# deadlocks.net
KiCad netlist of a schematic drawn in EAGLE
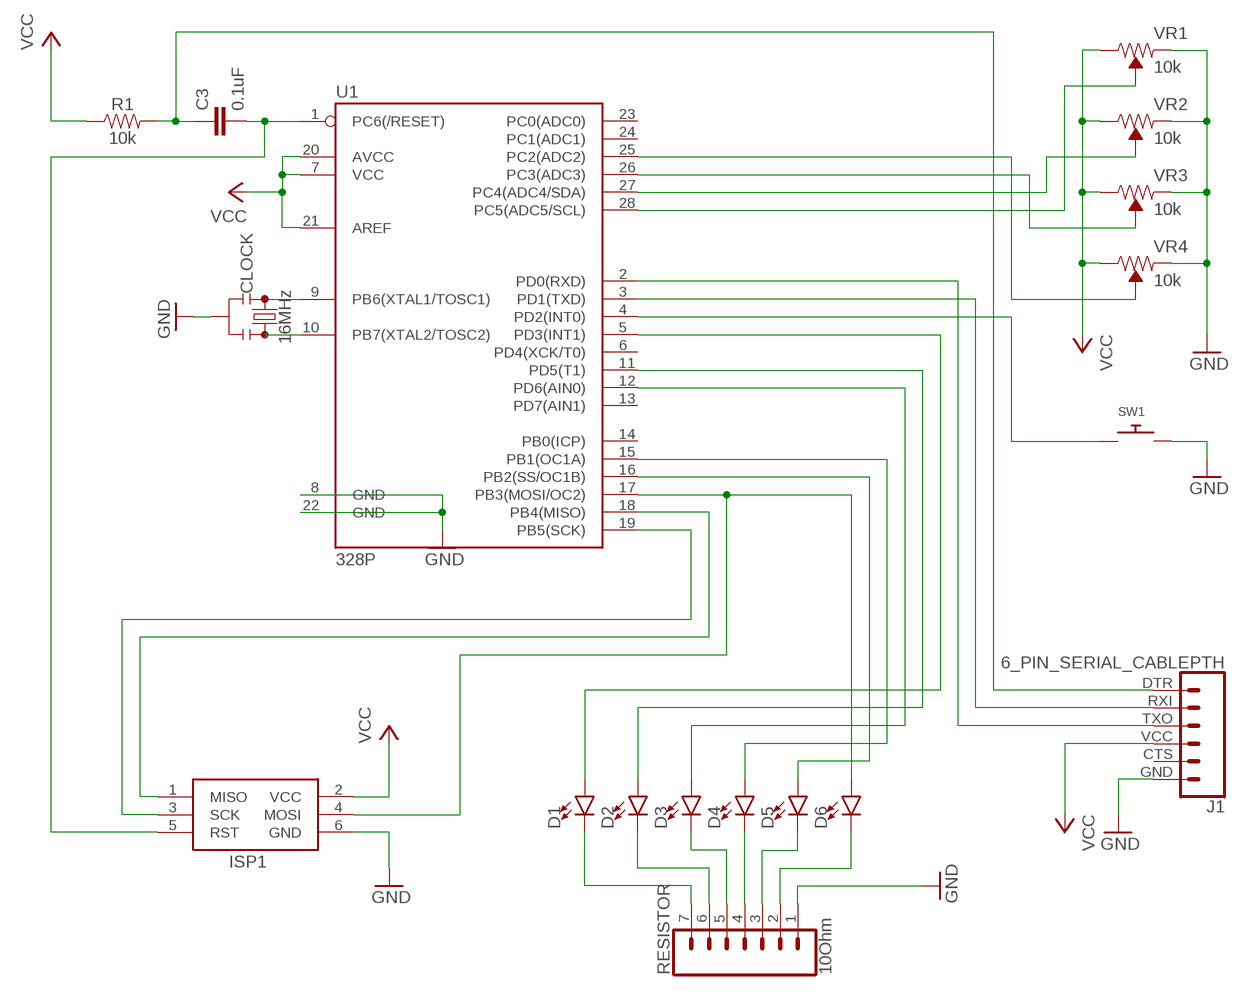
[diagram p0: schematic, sheet 1]

(export (version "E")
  (design (tool "Eeschema 10.0.6"))
  (components
    (comp (ref "C3")
      (value "0.1uF")
      (footprint "eagle-import:CAP-PTH-SMALL-KIT")
      (libsource (lib "eagle-import") (part "0.1UF-KIT-EZ-50V-20%"))
    )
    (comp (ref "CLOCK")
      (value "16MHz")
      (footprint "eagle-import:RESONATOR-PTH-7.6X3.8")
      (libsource (lib "eagle-import") (part "RESONATORPTH-7.6X3.8"))
    )
    (comp (ref "D1")
      (value "LED5MM")
      (footprint "eagle-import:LED_5MM")
      (libsource (lib "eagle-import") (part "LED5MM"))
    )
    (comp (ref "D2")
      (value "LED5MM")
      (footprint "eagle-import:LED_5MM")
      (libsource (lib "eagle-import") (part "LED5MM"))
    )
    (comp (ref "D3")
      (value "LED5MM")
      (footprint "eagle-import:LED_5MM")
      (libsource (lib "eagle-import") (part "LED5MM"))
    )
    (comp (ref "D4")
      (value "LED5MM")
      (footprint "eagle-import:LED_5MM")
      (libsource (lib "eagle-import") (part "LED5MM"))
    )
    (comp (ref "D5")
      (value "LED5MM")
      (footprint "eagle-import:LED_5MM")
      (libsource (lib "eagle-import") (part "LED5MM"))
    )
    (comp (ref "D6")
      (value "LED5MM")
      (footprint "eagle-import:LED_5MM")
      (libsource (lib "eagle-import") (part "LED5MM"))
    )
    (comp (ref "ISP1")
      (value "AVRISP-6")
      (footprint "eagle-import:AVRISP")
      (libsource (lib "eagle-import") (part "AVRISP-6"))
    )
    (comp (ref "J1")
      (value "6_PIN_SERIAL_CABLEPTH")
      (footprint "eagle-import:FTDI_BASIC")
      (libsource (lib "eagle-import") (part "6_PIN_SERIAL_CABLEPTH"))
    )
    (comp (ref "R1")
      (value "10k")
      (footprint "eagle-import:AXIAL-0.3")
      (libsource (lib "eagle-import") (part "10KOHM-HORIZ-1/4W-1%"))
    )
    (comp (ref "RESISTOR")
      (value "10Ohm")
      (footprint "eagle-import:1X07")
      (libsource (lib "eagle-import") (part "CONN_07"))
    )
    (comp (ref "SW1")
      (value "SWITCH_PUSHBUTTONEVQ-PE")
      (footprint "eagle-import:TACT_PANA-EVQ")
      (libsource (lib "eagle-import") (part "SWITCH_PUSHBUTTONEVQ-PE"))
    )
    (comp (ref "U1")
      (value "328P")
      (footprint "eagle-import:DIP28")
      (libsource (lib "eagle-import") (part "ATMEGA328P_PDIP"))
    )
    (comp (ref "VR1")
      (value "10k")
      (footprint "eagle-import:TRIMPOT-PTH-3386U")
      (libsource (lib "eagle-import") (part "TRIMPOT-PTH-10MM-KNOB-1/2W-10%"))
    )
    (comp (ref "VR2")
      (value "10k")
      (footprint "eagle-import:TRIMPOT-PTH-3386U")
      (libsource (lib "eagle-import") (part "TRIMPOT-PTH-10MM-KNOB-1/2W-10%"))
    )
    (comp (ref "VR3")
      (value "10k")
      (footprint "eagle-import:TRIMPOT-PTH-3386U")
      (libsource (lib "eagle-import") (part "TRIMPOT-PTH-10MM-KNOB-1/2W-10%"))
    )
    (comp (ref "VR4")
      (value "10k")
      (footprint "eagle-import:TRIMPOT-PTH-3386U")
      (libsource (lib "eagle-import") (part "TRIMPOT-PTH-10MM-KNOB-1/2W-10%"))
    )
  )
  (nets
    (net (code "1") (name "GND") (class "Default")
      (node (ref "CLOCK") (pin "2") (pinfunction "2_2") (pintype "passive"))
      (node (ref "ISP1") (pin "6") (pinfunction "GND_6") (pintype "power_in"))
      (node (ref "J1") (pin "GND") (pinfunction "6_GND") (pintype "passive"))
      (node (ref "RESISTOR") (pin "1") (pinfunction "1_1") (pintype "passive"))
      (node (ref "SW1") (pin "P$2") (pinfunction "P$2_P$2") (pintype "passive"))
      (node (ref "U1") (pin "22") (pinfunction "GND_22") (pintype "bidirectional"))
      (node (ref "U1") (pin "8") (pinfunction "GND_8") (pintype "bidirectional"))
      (node (ref "VR1") (pin "1") (pinfunction "CCW_1") (pintype "passive"))
      (node (ref "VR2") (pin "1") (pinfunction "CCW_1") (pintype "passive"))
      (node (ref "VR3") (pin "1") (pinfunction "CCW_1") (pintype "passive"))
      (node (ref "VR4") (pin "1") (pinfunction "CCW_1") (pintype "passive"))
    )
    (net (code "2") (name "Net-(D1-C)") (class "Default")
      (node (ref "D1") (pin "K") (pinfunction "C_K") (pintype "passive"))
      (node (ref "RESISTOR") (pin "7") (pinfunction "7_7") (pintype "passive"))
    )
    (net (code "3") (name "Net-(D2-C)") (class "Default")
      (node (ref "D2") (pin "K") (pinfunction "C_K") (pintype "passive"))
      (node (ref "RESISTOR") (pin "6") (pinfunction "6_6") (pintype "passive"))
    )
    (net (code "4") (name "Net-(D3-C)") (class "Default")
      (node (ref "D3") (pin "K") (pinfunction "C_K") (pintype "passive"))
      (node (ref "RESISTOR") (pin "5") (pinfunction "5_5") (pintype "passive"))
    )
    (net (code "5") (name "Net-(D4-C)") (class "Default")
      (node (ref "D4") (pin "K") (pinfunction "C_K") (pintype "passive"))
      (node (ref "RESISTOR") (pin "4") (pinfunction "4_4") (pintype "passive"))
    )
    (net (code "6") (name "Net-(D5-C)") (class "Default")
      (node (ref "D5") (pin "K") (pinfunction "C_K") (pintype "passive"))
      (node (ref "RESISTOR") (pin "3") (pinfunction "3_3") (pintype "passive"))
    )
    (net (code "7") (name "Net-(D6-C)") (class "Default")
      (node (ref "D6") (pin "K") (pinfunction "C_K") (pintype "passive"))
      (node (ref "RESISTOR") (pin "2") (pinfunction "2_2") (pintype "passive"))
    )
    (net (code "8") (name "Net-(ISP1-MISO)") (class "Default")
      (node (ref "ISP1") (pin "1") (pinfunction "MISO_1") (pintype "input"))
      (node (ref "U1") (pin "18") (pinfunction "PB4(MISO)_18") (pintype "bidirectional"))
    )
    (net (code "9") (name "Net-(ISP1-MOSI)") (class "Default")
      (node (ref "D6") (pin "A") (pinfunction "A_A") (pintype "passive"))
      (node (ref "ISP1") (pin "4") (pinfunction "MOSI_4") (pintype "output"))
      (node (ref "U1") (pin "17") (pinfunction "PB3(MOSI/OC2)_17") (pintype "bidirectional"))
    )
    (net (code "10") (name "Net-(ISP1-RST)") (class "Default")
      (node (ref "C3") (pin "2") (pinfunction "2_2") (pintype "passive"))
      (node (ref "ISP1") (pin "5") (pinfunction "RST_5") (pintype "output"))
      (node (ref "U1") (pin "1") (pinfunction "PC6(/RESET)_1") (pintype "bidirectional"))
    )
    (net (code "11") (name "Net-(ISP1-SCK)") (class "Default")
      (node (ref "ISP1") (pin "3") (pinfunction "SCK_3") (pintype "output"))
      (node (ref "U1") (pin "19") (pinfunction "PB5(SCK)_19") (pintype "bidirectional"))
    )
    (net (code "12") (name "Net-(J1-1)") (class "Default")
      (node (ref "C3") (pin "1") (pinfunction "1_1") (pintype "passive"))
      (node (ref "J1") (pin "DTR") (pinfunction "1_DTR") (pintype "passive"))
      (node (ref "R1") (pin "P$2") (pinfunction "2_P$2") (pintype "passive"))
    )
    (net (code "13") (name "Net-(J1-2)") (class "Default")
      (node (ref "J1") (pin "RXI") (pinfunction "2_RXI") (pintype "passive"))
      (node (ref "U1") (pin "3") (pinfunction "PD1(TXD)_3") (pintype "bidirectional"))
    )
    (net (code "14") (name "Net-(J1-3)") (class "Default")
      (node (ref "J1") (pin "TXO") (pinfunction "3_TXO") (pintype "passive"))
      (node (ref "U1") (pin "2") (pinfunction "PD0(RXD)_2") (pintype "bidirectional"))
    )
    (net (code "15") (name "Net-(U1-PB1(OC1A))") (class "Default")
      (node (ref "D4") (pin "A") (pinfunction "A_A") (pintype "passive"))
      (node (ref "U1") (pin "15") (pinfunction "PB1(OC1A)_15") (pintype "bidirectional"))
    )
    (net (code "16") (name "Net-(U1-PB2(SS{slash}OC1B))") (class "Default")
      (node (ref "D5") (pin "A") (pinfunction "A_A") (pintype "passive"))
      (node (ref "U1") (pin "16") (pinfunction "PB2(SS/OC1B)_16") (pintype "bidirectional"))
    )
    (net (code "17") (name "Net-(U1-PB6(XTAL1{slash}TOSC1))") (class "Default")
      (node (ref "CLOCK") (pin "1") (pinfunction "1_1") (pintype "passive"))
      (node (ref "U1") (pin "9") (pinfunction "PB6(XTAL1/TOSC1)_9") (pintype "bidirectional"))
    )
    (net (code "18") (name "Net-(U1-PB7(XTAL2{slash}TOSC2))") (class "Default")
      (node (ref "CLOCK") (pin "3") (pinfunction "3_3") (pintype "passive"))
      (node (ref "U1") (pin "10") (pinfunction "PB7(XTAL2/TOSC2)_10") (pintype "bidirectional"))
    )
    (net (code "19") (name "Net-(U1-PC2(ADC2))") (class "Default")
      (node (ref "U1") (pin "25") (pinfunction "PC2(ADC2)_25") (pintype "bidirectional"))
      (node (ref "VR4") (pin "2") (pinfunction "WIPER_2") (pintype "passive"))
    )
    (net (code "20") (name "Net-(U1-PC3(ADC3))") (class "Default")
      (node (ref "U1") (pin "26") (pinfunction "PC3(ADC3)_26") (pintype "bidirectional"))
      (node (ref "VR3") (pin "2") (pinfunction "WIPER_2") (pintype "passive"))
    )
    (net (code "21") (name "Net-(U1-PC4(ADC4{slash}SDA))") (class "Default")
      (node (ref "U1") (pin "27") (pinfunction "PC4(ADC4/SDA)_27") (pintype "bidirectional"))
      (node (ref "VR2") (pin "2") (pinfunction "WIPER_2") (pintype "passive"))
    )
    (net (code "22") (name "Net-(U1-PC5(ADC5{slash}SCL))") (class "Default")
      (node (ref "U1") (pin "28") (pinfunction "PC5(ADC5/SCL)_28") (pintype "bidirectional"))
      (node (ref "VR1") (pin "2") (pinfunction "WIPER_2") (pintype "passive"))
    )
    (net (code "23") (name "Net-(U1-PD2(INT0))") (class "Default")
      (node (ref "SW1") (pin "P$1") (pinfunction "P$1_P$1") (pintype "passive"))
      (node (ref "U1") (pin "4") (pinfunction "PD2(INT0)_4") (pintype "bidirectional"))
    )
    (net (code "24") (name "Net-(U1-PD3(INT1))") (class "Default")
      (node (ref "D1") (pin "A") (pinfunction "A_A") (pintype "passive"))
      (node (ref "U1") (pin "5") (pinfunction "PD3(INT1)_5") (pintype "bidirectional"))
    )
    (net (code "25") (name "Net-(U1-PD5(T1))") (class "Default")
      (node (ref "D2") (pin "A") (pinfunction "A_A") (pintype "passive"))
      (node (ref "U1") (pin "11") (pinfunction "PD5(T1)_11") (pintype "bidirectional"))
    )
    (net (code "26") (name "Net-(U1-PD6(AIN0))") (class "Default")
      (node (ref "D3") (pin "A") (pinfunction "A_A") (pintype "passive"))
      (node (ref "U1") (pin "12") (pinfunction "PD6(AIN0)_12") (pintype "bidirectional"))
    )
    (net (code "27") (name "VCC") (class "Default")
      (node (ref "ISP1") (pin "2") (pinfunction "VCC_2") (pintype "power_in"))
      (node (ref "J1") (pin "VCC") (pinfunction "4_VCC") (pintype "passive"))
      (node (ref "R1") (pin "P$1") (pinfunction "1_P$1") (pintype "passive"))
      (node (ref "U1") (pin "20") (pinfunction "AVCC_20") (pintype "bidirectional"))
      (node (ref "U1") (pin "21") (pinfunction "AREF_21") (pintype "bidirectional"))
      (node (ref "U1") (pin "7") (pinfunction "VCC_7") (pintype "bidirectional"))
      (node (ref "VR1") (pin "3") (pinfunction "CW_3") (pintype "passive"))
      (node (ref "VR2") (pin "3") (pinfunction "CW_3") (pintype "passive"))
      (node (ref "VR3") (pin "3") (pinfunction "CW_3") (pintype "passive"))
      (node (ref "VR4") (pin "3") (pinfunction "CW_3") (pintype "passive"))
    )
    (net (code "28") (name "unconnected-(J1-5-PadCTS)") (class "Default")
      (node (ref "J1") (pin "CTS") (pinfunction "5_CTS") (pintype "passive"))
    )
    (net (code "29") (name "unconnected-(U1-PB0(ICP)-Pad14)") (class "Default")
      (node (ref "U1") (pin "14") (pinfunction "PB0(ICP)_14") (pintype "bidirectional"))
    )
    (net (code "30") (name "unconnected-(U1-PC0(ADC0)-Pad23)") (class "Default")
      (node (ref "U1") (pin "23") (pinfunction "PC0(ADC0)_23") (pintype "bidirectional"))
    )
    (net (code "31") (name "unconnected-(U1-PC1(ADC1)-Pad24)") (class "Default")
      (node (ref "U1") (pin "24") (pinfunction "PC1(ADC1)_24") (pintype "bidirectional"))
    )
    (net (code "32") (name "unconnected-(U1-PD4(XCK{slash}T0)-Pad6)") (class "Default")
      (node (ref "U1") (pin "6") (pinfunction "PD4(XCK/T0)_6") (pintype "bidirectional"))
    )
    (net (code "33") (name "unconnected-(U1-PD7(AIN1)-Pad13)") (class "Default")
      (node (ref "U1") (pin "13") (pinfunction "PD7(AIN1)_13") (pintype "bidirectional"))
    )
  )
)
